# Acoustic_Light_Motion_Sensors.net
KiCad netlist of a schematic drawn in Altium Designer
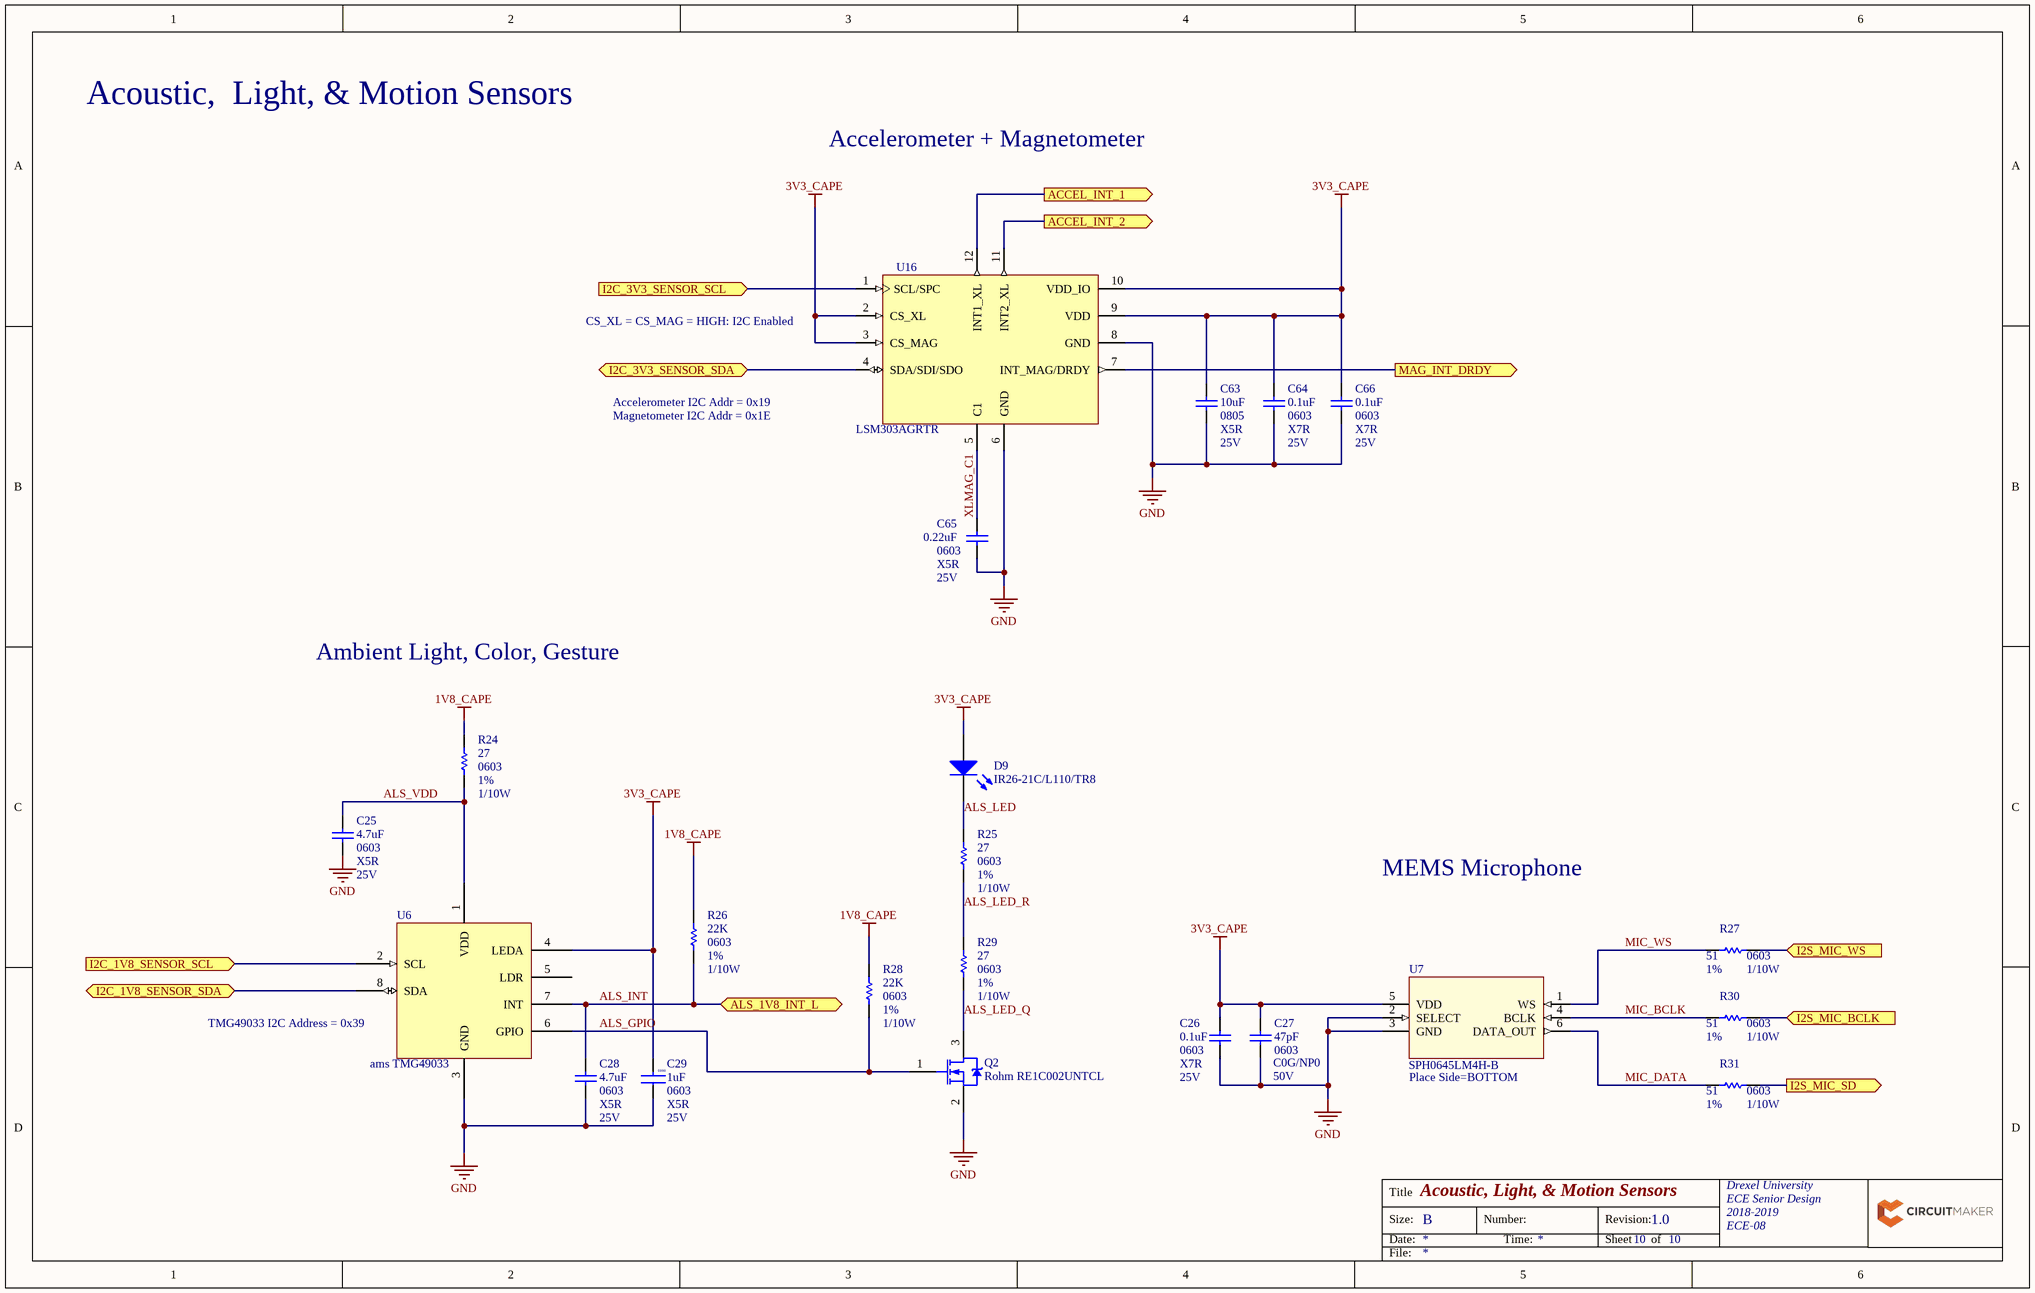
[diagram p0: Acoustic, Light, Motion Sensors.SchDoc]

(export (version "E")
  (design (tool "Eeschema 10.0.6"))
  (components
    (comp (ref "C25")
      (value "Murata GRM188R61E475KE11D")
      (footprint "CAPC1608X90X35ML10T15")
      (description "CAP CER 4.7UF 25V 10% X5R 0603")
      (fields
        (field (name "CAPACITANCE") "4.7uF")
        (field (name "CASE/PACKAGE") "0603")
        (field (name "DIELECTRIC CHARACTERISTIC") "X5R")
        (field (name "VOLTAGE RATING (DC)") "25V")
        (field (name "MANUFACTURER PART NUMBER") "GRM188R61E475KE11D")
      )
      (libsource (lib "CommunityVault") (part "CMP-8856396-4"))
    )
    (comp (ref "C26")
      (value "Würth Elektronik 885012206071")
      (footprint "PCB-8usp83j76ntw2xroyu3n-1")
      (description "Multilayer Ceramic Capacitor, WCAP-CSGP Series, 0.1 F, 10%, X7R, 25 V, 0603 [1608 Metric]")
      (fields
        (field (name "DIELECTRIC CHARACTERISTIC") "X7R")
        (field (name "VOLTAGE RATING (DC)") "25V")
        (field (name "CAPACITANCE") "0.1uF")
        (field (name "MANUFACTURER PART NUMBER") "885012206071")
        (field (name "PACKAGE") "0603")
      )
      (libsource (lib "CommunityVault") (part "CMP-034ac9768ab0dc8d-1"))
    )
    (comp (ref "C27")
      (value "Würth Elektronik 885012006055")
      (footprint "PCB-6hp2bdit6vqlyhs5eujf-1")
      (description "Cap, Mlcc, Np0, 47Pf, 50V, 0603")
      (fields
        (field (name "MANUFACTURER PART NUMBER") "885012006055")
        (field (name "CAPACITANCE") "47pF")
        (field (name "DIELECTRIC CHARACTERISTIC") "C0G/NP0")
        (field (name "VOLTAGE RATING (DC)") "50V")
        (field (name "PACKAGE") "0603")
      )
      (libsource (lib "CommunityVault") (part "CMP-bdcf7723a1936208-1"))
    )
    (comp (ref "C28")
      (value "Murata GRM188R61E475KE11D")
      (footprint "CAPC1608X90X35ML10T15")
      (description "CAP CER 4.7UF 25V 10% X5R 0603")
      (fields
        (field (name "CAPACITANCE") "4.7uF")
        (field (name "CASE/PACKAGE") "0603")
        (field (name "DIELECTRIC CHARACTERISTIC") "X5R")
        (field (name "VOLTAGE RATING (DC)") "25V")
        (field (name "MANUFACTURER PART NUMBER") "GRM188R61E475KE11D")
      )
      (libsource (lib "CommunityVault") (part "CMP-8856396-4"))
    )
    (comp (ref "C29")
      (value "Taiyo Yuden TMK107BJ105KA-T")
      (footprint "PCB-bncvufzharetcg4gy1u6-1")
      (description "Cap Ceramic 1uF 25V X5R 10% SMD 0603 85°C Paper T/R")
      (fields
        (field (name "CASE/PACKAGE") "0603")
        (field (name "DIELECTRIC CHARACTERISTIC") "X5R")
        (field (name "CAPACITANCE") "1uF")
        (field (name "VOLTAGE RATING (DC)") "25V")
        (field (name "MANUFACTURER PART NUMBER") "TMK107BJ105KA-T")
      )
      (libsource (lib "CommunityVault") (part "CMP-ac4e65478e587389-1"))
    )
    (comp (ref "C63")
      (value "Murata GRM21BR61E106MA73L")
      (footprint "Capacitor_0805")
      (description "0805 25 V 10 uF ±20% Tolerance X5R Multilayer Ceramic Capacitor")
      (fields
        (field (name "VOLTAGE RATING (DC)") "25V")
        (field (name "PACKAGE") "0805")
        (field (name "CAPACITANCE") "10uF")
        (field (name "TEMPERATURE COEFFICIENT") "X5R")
      )
      (libsource (lib "CommunityVault") (part "CMP-3dadf66f6462e26a-3"))
    )
    (comp (ref "C64")
      (value "Würth Elektronik 885012206071")
      (footprint "PCB-8usp83j76ntw2xroyu3n-1")
      (description "Multilayer Ceramic Capacitor, WCAP-CSGP Series, 0.1 F, 10%, X7R, 25 V, 0603 [1608 Metric]")
      (fields
        (field (name "DIELECTRIC CHARACTERISTIC") "X7R")
        (field (name "VOLTAGE RATING (DC)") "25V")
        (field (name "CAPACITANCE") "0.1uF")
        (field (name "MANUFACTURER PART NUMBER") "885012206071")
        (field (name "PACKAGE") "0603")
      )
      (libsource (lib "CommunityVault") (part "CMP-034ac9768ab0dc8d-1"))
    )
    (comp (ref "C65")
      (value "Würth Elektronik 885012106019")
      (footprint "PCB-eliu6zwwm13rwakn7csa-1")
      (description "Cap Cer 0.22UF 25V X5R 0603")
      (fields
        (field (name "MANUFACTURER PART NO.") "885012106019")
        (field (name "CASE/PACKAGE") "0603")
        (field (name "CAPACITANCE") "0.22uF")
        (field (name "TEMPERATURE COEFFICIENT") "X5R")
        (field (name "VOLTAGE RATING") "25V")
      )
      (libsource (lib "CommunityVault") (part "CMP-d2ee18d25bec0d29-1"))
    )
    (comp (ref "C66")
      (value "Würth Elektronik 885012206071")
      (footprint "PCB-8usp83j76ntw2xroyu3n-1")
      (description "Multilayer Ceramic Capacitor, WCAP-CSGP Series, 0.1 F, 10%, X7R, 25 V, 0603 [1608 Metric]")
      (fields
        (field (name "DIELECTRIC CHARACTERISTIC") "X7R")
        (field (name "VOLTAGE RATING (DC)") "25V")
        (field (name "CAPACITANCE") "0.1uF")
        (field (name "MANUFACTURER PART NUMBER") "885012206071")
        (field (name "PACKAGE") "0603")
      )
      (libsource (lib "CommunityVault") (part "CMP-034ac9768ab0dc8d-1"))
    )
    (comp (ref "D9")
      (value "IR26-21C/L110/TR8")
      (footprint "1206_A")
      (description "LED IR SUBMINI 1.6MM ROUND SMD")
      (libsource (lib "CommunityVault") (part "CMP-1542916-2"))
    )
    (comp (ref "Q2")
      (value "Rohm RE1C002UNTCL")
      (footprint "PCB-cy8fr5d7bejv46iuepu9-1")
      (description "MOSFET N-CH 20V 0.2A EMT3")
      (fields
        (field (name "MANUFACTURER") "Rohm Semiconductor")
        (field (name "MANUFACTURER PART NUMBER") "RE1C002UNTCL")
      )
      (libsource (lib "CommunityVault") (part "SYM-817649b5405f5eb1-1"))
    )
    (comp (ref "R24")
      (value "Panasonic / Panasonic ECG ERJ-3EKF27R0V")
      (footprint "0603-RES")
      (description "Res Thick Film 0603 27 Ohm 1% 0.1W(1/10W) ±100ppm/C Molded SMD Automotive Punched T/R")
      (fields
        (field (name "MANUFACTURER PART NUMBER") "ERJ-3EKF27R0V")
        (field (name "RESISTANCE") "27")
        (field (name "POWER RATING") "1/10W")
        (field (name "CASE/PACKAGE") "0603")
        (field (name "RESISTANCE TOLERANCE") "1%")
      )
      (libsource (lib "CommunityVault") (part "CMP-f61f3f990ffb29d8-2"))
    )
    (comp (ref "R25")
      (value "Panasonic / Panasonic ECG ERJ-3EKF27R0V")
      (footprint "0603-RES")
      (description "Res Thick Film 0603 27 Ohm 1% 0.1W(1/10W) ±100ppm/C Molded SMD Automotive Punched T/R")
      (fields
        (field (name "MANUFACTURER PART NUMBER") "ERJ-3EKF27R0V")
        (field (name "RESISTANCE") "27")
        (field (name "POWER RATING") "1/10W")
        (field (name "CASE/PACKAGE") "0603")
        (field (name "RESISTANCE TOLERANCE") "1%")
      )
      (libsource (lib "CommunityVault") (part "CMP-f61f3f990ffb29d8-2"))
    )
    (comp (ref "R26")
      (value "Yageo RC0603FR-0722KL")
      (footprint "RESC1608X55X25LL10T15")
      (description "Chip Resistor, 22 KOhm, +/- 1%, 0.1 W, -55 to 155 degC, 0603 (1608 Metric), RoHS, Tape and Reel")
      (fields
        (field (name "RESISTANCE") "22K")
        (field (name "RESISTANCE TOLERANCE") "1%")
        (field (name "CASE/PACKAGE") "0603")
        (field (name "POWER RATING") "1/10W")
        (field (name "MANUFACTURER PART NUMBER") "RC0603FR-0722KL")
      )
      (libsource (lib "CommunityVault") (part "CMP-1853446-5"))
    )
    (comp (ref "R27")
      (value "Stackpole Electronics RMCF0603FT51R0")
      (footprint "PCB-9ahxsq8gddjqcnfjmojj-1")
      (description "Res Thick Film 0603 51 Ohm 1% 0.1W(1/10W) ???}100ppm/??? Molded SMD Automotive Paper T/R")
      (fields
        (field (name "CASE/PACKAGE") "0603")
        (field (name "MANUFACTURER PART NUMBER") "RMCF0603FT51R0")
        (field (name "POWER RATING") "1/10W")
        (field (name "RESISTANCE") "51")
        (field (name "RESISTANCE TOLERANCE") "1%")
      )
      (libsource (lib "CommunityVault") (part "CMP-c18a09a5cf0a1e4d-2"))
    )
    (comp (ref "R28")
      (value "Yageo RC0603FR-0722KL")
      (footprint "RESC1608X55X25LL10T15")
      (description "Chip Resistor, 22 KOhm, +/- 1%, 0.1 W, -55 to 155 degC, 0603 (1608 Metric), RoHS, Tape and Reel")
      (fields
        (field (name "RESISTANCE") "22K")
        (field (name "RESISTANCE TOLERANCE") "1%")
        (field (name "CASE/PACKAGE") "0603")
        (field (name "POWER RATING") "1/10W")
        (field (name "MANUFACTURER PART NUMBER") "RC0603FR-0722KL")
      )
      (libsource (lib "CommunityVault") (part "CMP-1853446-5"))
    )
    (comp (ref "R29")
      (value "Panasonic / Panasonic ECG ERJ-3EKF27R0V")
      (footprint "0603-RES")
      (description "Res Thick Film 0603 27 Ohm 1% 0.1W(1/10W) ±100ppm/C Molded SMD Automotive Punched T/R")
      (fields
        (field (name "MANUFACTURER PART NUMBER") "ERJ-3EKF27R0V")
        (field (name "RESISTANCE") "27")
        (field (name "POWER RATING") "1/10W")
        (field (name "CASE/PACKAGE") "0603")
        (field (name "RESISTANCE TOLERANCE") "1%")
      )
      (libsource (lib "CommunityVault") (part "CMP-f61f3f990ffb29d8-2"))
    )
    (comp (ref "R30")
      (value "Stackpole Electronics RMCF0603FT51R0")
      (footprint "PCB-9ahxsq8gddjqcnfjmojj-1")
      (description "Res Thick Film 0603 51 Ohm 1% 0.1W(1/10W) ???}100ppm/??? Molded SMD Automotive Paper T/R")
      (fields
        (field (name "CASE/PACKAGE") "0603")
        (field (name "MANUFACTURER PART NUMBER") "RMCF0603FT51R0")
        (field (name "POWER RATING") "1/10W")
        (field (name "RESISTANCE") "51")
        (field (name "RESISTANCE TOLERANCE") "1%")
      )
      (libsource (lib "CommunityVault") (part "CMP-c18a09a5cf0a1e4d-2"))
    )
    (comp (ref "R31")
      (value "Stackpole Electronics RMCF0603FT51R0")
      (footprint "PCB-9ahxsq8gddjqcnfjmojj-1")
      (description "Res Thick Film 0603 51 Ohm 1% 0.1W(1/10W) ???}100ppm/??? Molded SMD Automotive Paper T/R")
      (fields
        (field (name "CASE/PACKAGE") "0603")
        (field (name "MANUFACTURER PART NUMBER") "RMCF0603FT51R0")
        (field (name "POWER RATING") "1/10W")
        (field (name "RESISTANCE") "51")
        (field (name "RESISTANCE TOLERANCE") "1%")
      )
      (libsource (lib "CommunityVault") (part "CMP-c18a09a5cf0a1e4d-2"))
    )
    (comp (ref "U6")
      (value "ams TMG49033")
      (footprint "LGA8C102P2X4_200X500X107")
      (description "Gesture, Color and Proximity Sensor Module Digital Output 1.8V 8-Pin T/R")
      (libsource (lib "CommunityVault") (part "CMP-5d86977545368241-2"))
    )
    (comp (ref "U7")
      (value "PH0645LM4H-B")
      (footprint "SPH-MEMS")
      (description "Mic Mems Digital I2s Omni -26db")
      (fields (field (name "MANUFACTURER PART NUMBER") "SPH0645LM4H-B"))
      (libsource (lib "CommunityVault") (part "CMP-f6813c2c61792946-5"))
    )
    (comp (ref "U16")
      (value "LSM303AGRTR")
      (footprint "PCB-zxk1k6ks26krobft08qb-1")
      (libsource (lib "CommunityVault") (part "SYM-98f6527696964731-1"))
    )
  )
  (nets
    (net (code "1") (name "/ACCEL_INT_1") (class "Default")
      (node (ref "U16") (pin "12") (pinfunction "INT1_XL_12") (pintype "output"))
    )
    (net (code "2") (name "/ACCEL_INT_2") (class "Default")
      (node (ref "U16") (pin "11") (pinfunction "INT2_XL_11") (pintype "output"))
    )
    (net (code "3") (name "/ALS_GPIO") (class "Default")
      (node (ref "Q2") (pin "1") (pinfunction "G_1") (pintype "passive"))
      (node (ref "R28") (pin "1") (pinfunction "1_1") (pintype "passive"))
      (node (ref "U6") (pin "6") (pinfunction "GPIO_6") (pintype "open_collector"))
    )
    (net (code "4") (name "/ALS_INT") (class "Default")
      (node (ref "C28") (pin "1") (pinfunction "1_1") (pintype "passive"))
      (node (ref "R26") (pin "1") (pinfunction "1_1") (pintype "passive"))
      (node (ref "U6") (pin "7") (pinfunction "INT_7") (pintype "open_collector"))
    )
    (net (code "5") (name "/ALS_LED") (class "Default")
      (node (ref "D9") (pin "2") (pinfunction "2_2") (pintype "passive"))
      (node (ref "R25") (pin "2") (pinfunction "2_2") (pintype "passive"))
    )
    (net (code "6") (name "/ALS_LED_Q") (class "Default")
      (node (ref "Q2") (pin "3") (pinfunction "D_3") (pintype "passive"))
      (node (ref "R29") (pin "1") (pinfunction "1_1") (pintype "passive"))
    )
    (net (code "7") (name "/ALS_LED_R") (class "Default")
      (node (ref "R25") (pin "1") (pinfunction "1_1") (pintype "passive"))
      (node (ref "R29") (pin "2") (pinfunction "2_2") (pintype "passive"))
    )
    (net (code "8") (name "/ALS_VDD") (class "Default")
      (node (ref "C25") (pin "1") (pinfunction "1_1") (pintype "passive"))
      (node (ref "R24") (pin "1") (pinfunction "1_1") (pintype "passive"))
      (node (ref "U6") (pin "1") (pinfunction "VDD_1") (pintype "power_in"))
    )
    (net (code "9") (name "/I2C_1V8_SENSOR_SCL") (class "Default")
      (node (ref "U6") (pin "2") (pinfunction "SCL_2") (pintype "input"))
    )
    (net (code "10") (name "/I2C_1V8_SENSOR_SDA") (class "Default")
      (node (ref "U6") (pin "8") (pinfunction "SDA_8") (pintype "bidirectional"))
    )
    (net (code "11") (name "/I2C_3V3_SENSOR_SCL") (class "Default")
      (node (ref "U16") (pin "1") (pinfunction "SCL/SPC_1") (pintype "input"))
    )
    (net (code "12") (name "/I2C_3V3_SENSOR_SDA") (class "Default")
      (node (ref "U16") (pin "4") (pinfunction "SDA/SDI/SDO_4") (pintype "bidirectional"))
    )
    (net (code "13") (name "/I2S_MIC_BCLK") (class "Default")
      (node (ref "R30") (pin "2") (pinfunction "2_2") (pintype "passive"))
    )
    (net (code "14") (name "/I2S_MIC_SD") (class "Default")
      (node (ref "R31") (pin "2") (pinfunction "2_2") (pintype "passive"))
    )
    (net (code "15") (name "/I2S_MIC_WS") (class "Default")
      (node (ref "R27") (pin "2") (pinfunction "2_2") (pintype "passive"))
    )
    (net (code "16") (name "/MAG_INT_DRDY") (class "Default")
      (node (ref "U16") (pin "7") (pinfunction "INT_MAG/DRDY_7") (pintype "output"))
    )
    (net (code "17") (name "/MIC_BCLK") (class "Default")
      (node (ref "R30") (pin "1") (pinfunction "1_1") (pintype "passive"))
      (node (ref "U7") (pin "4") (pinfunction "BCLK_4") (pintype "input"))
    )
    (net (code "18") (name "/MIC_DATA") (class "Default")
      (node (ref "R31") (pin "1") (pinfunction "1_1") (pintype "passive"))
      (node (ref "U7") (pin "6") (pinfunction "DATA_OUT_6") (pintype "output"))
    )
    (net (code "19") (name "/MIC_WS") (class "Default")
      (node (ref "R27") (pin "1") (pinfunction "1_1") (pintype "passive"))
      (node (ref "U7") (pin "1") (pinfunction "WS_1") (pintype "input"))
    )
    (net (code "20") (name "/XLMAG_C1") (class "Default")
      (node (ref "C65") (pin "2") (pinfunction "2_2") (pintype "passive"))
      (node (ref "U16") (pin "5") (pinfunction "C1_5") (pintype "passive"))
    )
    (net (code "21") (name "1V8_CAPE") (class "Default")
      (node (ref "R24") (pin "2") (pinfunction "2_2") (pintype "passive"))
      (node (ref "R26") (pin "2") (pinfunction "2_2") (pintype "passive"))
      (node (ref "R28") (pin "2") (pinfunction "2_2") (pintype "passive"))
    )
    (net (code "22") (name "3V3_CAPE") (class "Default")
      (node (ref "C26") (pin "2") (pinfunction "2_2") (pintype "passive"))
      (node (ref "C27") (pin "2") (pinfunction "2_2") (pintype "passive"))
      (node (ref "C29") (pin "2") (pinfunction "2_2") (pintype "passive"))
      (node (ref "C63") (pin "2") (pinfunction "2_2") (pintype "passive"))
      (node (ref "C64") (pin "2") (pinfunction "2_2") (pintype "passive"))
      (node (ref "C66") (pin "2") (pinfunction "2_2") (pintype "passive"))
      (node (ref "D9") (pin "1") (pinfunction "1_1") (pintype "passive"))
      (node (ref "U16") (pin "10") (pinfunction "VDD_IO_10") (pintype "power_in"))
      (node (ref "U16") (pin "2") (pinfunction "CS_XL_2") (pintype "input"))
      (node (ref "U16") (pin "3") (pinfunction "CS_MAG_3") (pintype "input"))
      (node (ref "U16") (pin "9") (pinfunction "VDD_9") (pintype "power_in"))
      (node (ref "U6") (pin "4") (pinfunction "LEDA_4") (pintype "passive"))
      (node (ref "U7") (pin "5") (pinfunction "VDD_5") (pintype "power_in"))
    )
    (net (code "23") (name "GND") (class "Default")
      (node (ref "C25") (pin "2") (pinfunction "2_2") (pintype "passive"))
      (node (ref "C26") (pin "1") (pinfunction "1_1") (pintype "passive"))
      (node (ref "C27") (pin "1") (pinfunction "1_1") (pintype "passive"))
      (node (ref "C28") (pin "2") (pinfunction "2_2") (pintype "passive"))
      (node (ref "C29") (pin "1") (pinfunction "1_1") (pintype "passive"))
      (node (ref "C63") (pin "1") (pinfunction "1_1") (pintype "passive"))
      (node (ref "C64") (pin "1") (pinfunction "1_1") (pintype "passive"))
      (node (ref "C65") (pin "1") (pinfunction "1_1") (pintype "passive"))
      (node (ref "C66") (pin "1") (pinfunction "1_1") (pintype "passive"))
      (node (ref "Q2") (pin "2") (pinfunction "S_2") (pintype "passive"))
      (node (ref "U16") (pin "6") (pinfunction "GND_6") (pintype "power_in"))
      (node (ref "U16") (pin "8") (pinfunction "GND_8") (pintype "power_in"))
      (node (ref "U6") (pin "3") (pinfunction "GND_3") (pintype "power_in"))
      (node (ref "U7") (pin "2") (pinfunction "SELECT_2") (pintype "input"))
      (node (ref "U7") (pin "3") (pinfunction "GND_3") (pintype "power_in"))
    )
    (net (code "24") (name "unconnected-(U6-LDR-Pad5)") (class "Default")
      (node (ref "U6") (pin "5") (pinfunction "LDR_5") (pintype "passive"))
    )
  )
)
